# Receiver.net
KiCad netlist of a schematic drawn in Altium Designer
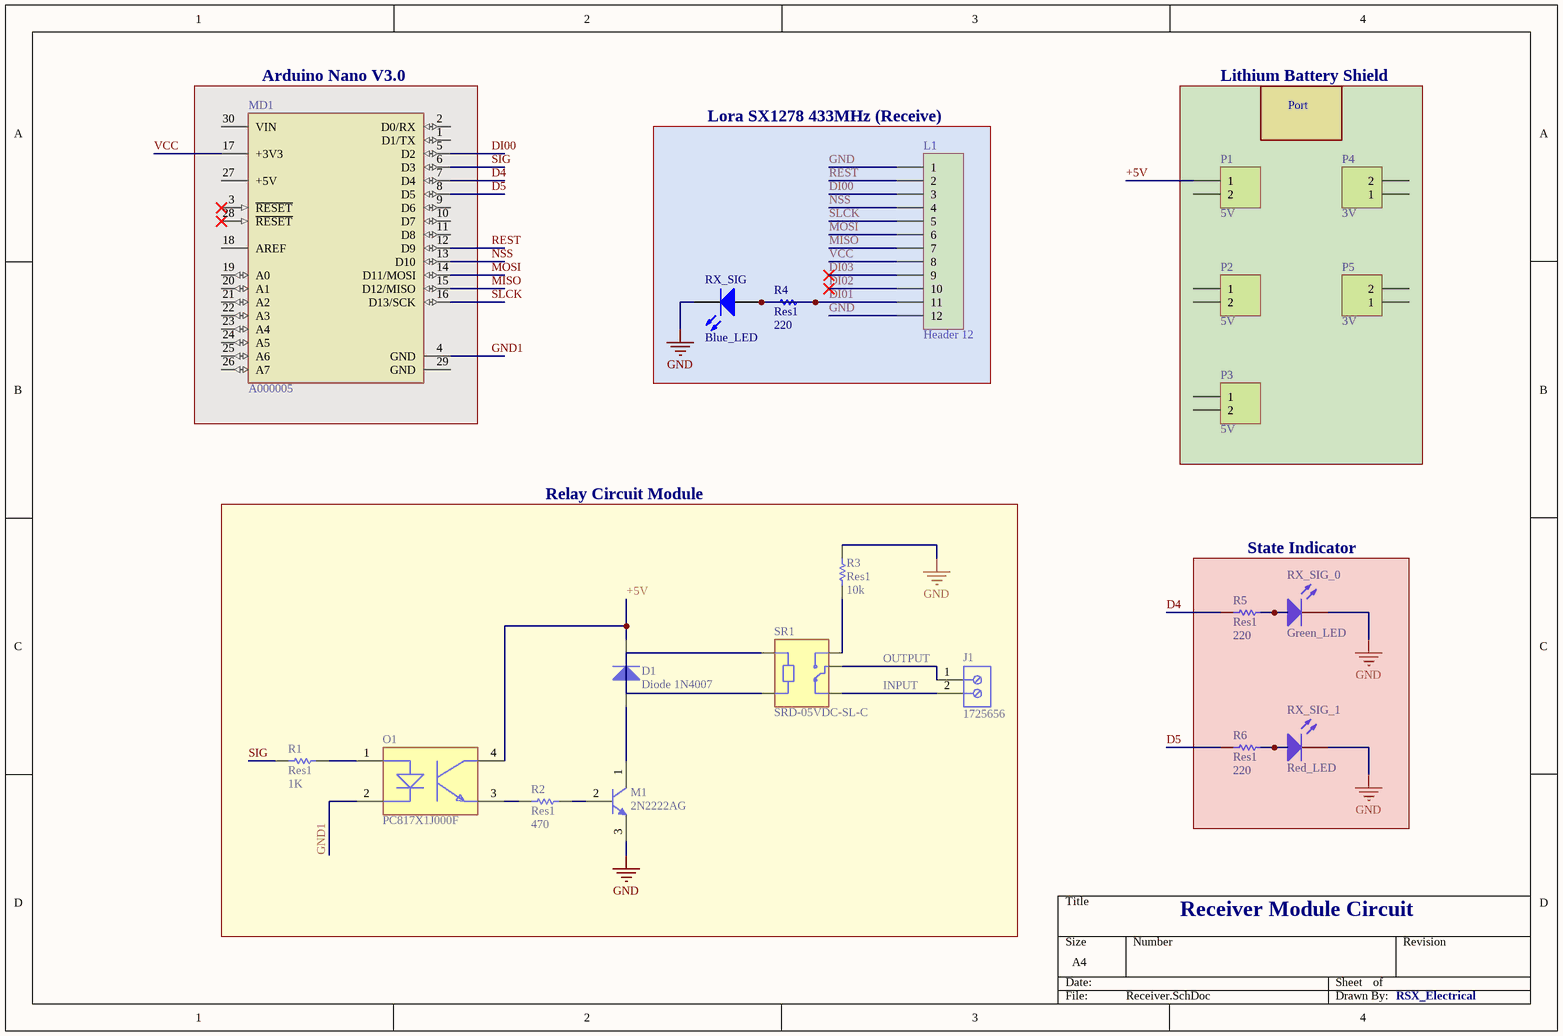
[diagram p0: Receiver.SchDoc]

(export (version "E")
  (design (tool "Eeschema 10.0.6"))
  (components
    (comp (ref "D1")
      (value "Diode 1N4007")
      (footprint "DO-41")
      (description "1 Amp General Purpose Rectifier")
      (fields (field (name "PUBLISHER") "Altium Limited"))
      (libsource (lib "Miscellaneous Devices") (part "Diode 1N4007"))
    )
    (comp (ref "J1")
      (value "1725656")
      (footprint "PHOE-1725656-2")
      (description "Male Header, Pitch 2.54 mm, 1 x 2 Position, Height 9 mm, Tail Length 3.5 mm")
      (fields (field (name "MANUFACTURER") "Phoenix Contact"))
      (libsource (lib "Altium Content Vault") (part "CN-1P-F-TB2"))
    )
    (comp (ref "L1")
      (value "Header 12")
      (footprint "HDR1X12")
      (description "Header, 12-Pin")
      (fields (field (name "PUBLISHER") "Altium Limited"))
      (libsource (lib "Miscellaneous Connectors") (part "Header 12"))
    )
    (comp (ref "M1")
      (value "2N2222AG")
      (footprint "ONSC-TO-92-3-29-11")
      (description "Amplifier Transistor, NPN Silicon, 3-Pin TO-92, Pb-Free, Bulk Box")
      (fields (field (name "PARTNUMBER") "P2N2222AG") (field (name "MANUFACTURER") "On Semiconductor"))
      (libsource (lib "Altium Content Vault") (part "ONSC-NPN-C1B2E3-3"))
    )
    (comp (ref "MD1")
      (value "A000005")
      (footprint "FP-A000005-MFG")
      (description "ARDUINO NANO ATMEGA328 EVAL BRD")
      (libsource (lib "Altium Content Vault") (part "d190c066e99afd1c6882cf92e11b2cc"))
    )
    (comp (ref "O1")
      (value "PC817X1J000F")
      (footprint "FP-PC817X1J000F-MFG")
      (description "OPTOISOLATOR 5KV TRANS 4DIP")
      (libsource (lib "Altium Content Vault") (part "8d9d817270a4e8f0d794346117f6aa3"))
    )
    (comp (ref "P1")
      (value "5V")
      (footprint "HDR1X2")
      (description "Header, 2-Pin")
      (fields (field (name "PUBLISHER") "Altium Limited"))
      (libsource (lib "") (part "Header 2_1"))
    )
    (comp (ref "P2")
      (value "5V")
      (footprint "HDR1X2")
      (description "Header, 2-Pin")
      (fields (field (name "PUBLISHER") "Altium Limited"))
      (libsource (lib "") (part "Header 2_1"))
    )
    (comp (ref "P3")
      (value "5V")
      (footprint "HDR1X2")
      (description "Header, 2-Pin")
      (fields (field (name "PUBLISHER") "Altium Limited"))
      (libsource (lib "") (part "Header 2_1"))
    )
    (comp (ref "P4")
      (value "3V")
      (footprint "HDR1X2")
      (description "Header, 2-Pin")
      (fields (field (name "PUBLISHER") "Altium Limited"))
      (libsource (lib "Miscellaneous Connectors") (part "Header 2"))
    )
    (comp (ref "P5")
      (value "3V")
      (footprint "HDR1X2")
      (description "Header, 2-Pin")
      (fields (field (name "PUBLISHER") "Altium Limited"))
      (libsource (lib "Miscellaneous Connectors") (part "Header 2"))
    )
    (comp (ref "R1")
      (value "Res1")
      (footprint "AXIAL-0.3")
      (description "Resistor")
      (fields (field (name "ALTIUM_VALUE") "1K") (field (name "PUBLISHER") "Altium Limited"))
      (libsource (lib "Miscellaneous Devices") (part "Res1"))
    )
    (comp (ref "R2")
      (value "Res1")
      (footprint "AXIAL-0.3")
      (description "Resistor")
      (fields (field (name "ALTIUM_VALUE") "470") (field (name "PUBLISHER") "Altium Limited"))
      (libsource (lib "Miscellaneous Devices") (part "Res1"))
    )
    (comp (ref "R3")
      (value "Res1")
      (footprint "AXIAL-0.3")
      (description "Resistor")
      (fields (field (name "ALTIUM_VALUE") "10k") (field (name "PUBLISHER") "Altium Limited"))
      (libsource (lib "Miscellaneous Devices") (part "Res1"))
    )
    (comp (ref "R4")
      (value "Res1")
      (footprint "AXIAL-0.3")
      (description "Resistor")
      (fields (field (name "ALTIUM_VALUE") "220") (field (name "PUBLISHER") "Altium Limited"))
      (libsource (lib "Miscellaneous Devices") (part "Res1"))
    )
    (comp (ref "R5")
      (value "Res1")
      (footprint "AXIAL-0.3")
      (description "Resistor")
      (fields (field (name "ALTIUM_VALUE") "220") (field (name "PUBLISHER") "Altium Limited"))
      (libsource (lib "Miscellaneous Devices") (part "Res1"))
    )
    (comp (ref "R6")
      (value "Res1")
      (footprint "AXIAL-0.3")
      (description "Resistor")
      (fields (field (name "ALTIUM_VALUE") "220") (field (name "PUBLISHER") "Altium Limited"))
      (libsource (lib "Miscellaneous Devices") (part "Res1"))
    )
    (comp (ref "RX_SIG")
      (value "Blue_LED")
      (footprint "LED-0")
      (description "Typical INFRARED GaAs LED")
      (fields (field (name "PUBLISHER") "Altium Limited"))
      (libsource (lib "Miscellaneous Devices") (part "LED0"))
    )
    (comp (ref "RX_SIG_0")
      (value "Green_LED")
      (footprint "LED-0")
      (description "Typical INFRARED GaAs LED")
      (fields (field (name "PUBLISHER") "Altium Limited"))
      (libsource (lib "Miscellaneous Devices") (part "LED0"))
    )
    (comp (ref "RX_SIG_1")
      (value "Red_LED")
      (footprint "LED-0")
      (description "Typical INFRARED GaAs LED")
      (fields (field (name "PUBLISHER") "Altium Limited"))
      (libsource (lib "Miscellaneous Devices") (part "LED0"))
    )
    (comp (ref "SR1")
      (value "SRD-05VDC-SL-C")
      (footprint "RELAY_SRD-05VDC-SL-C")
      (fields (field (name "MF") "Songle Relay"))
      (libsource (lib "SRD-05VDC-SL-C") (part "SRD-05VDC-SL-C"))
    )
  )
  (nets
    (net (code "1") (name "/+5V") (class "Default")
      (node (ref "D1") (pin "2") (pinfunction "K_2") (pintype "passive"))
      (node (ref "O1") (pin "4") (pinfunction "C_4") (pintype "passive"))
      (node (ref "P1") (pin "1") (pinfunction "1_1") (pintype "passive"))
    )
    (net (code "2") (name "/D4") (class "Default")
      (node (ref "MD1") (pin "7") (pinfunction "D4_7") (pintype "bidirectional"))
      (node (ref "R5") (pin "2") (pinfunction "2_2") (pintype "passive"))
    )
    (net (code "3") (name "/D5") (class "Default")
      (node (ref "MD1") (pin "8") (pinfunction "D5_8") (pintype "bidirectional"))
      (node (ref "R6") (pin "2") (pinfunction "2_2") (pintype "passive"))
    )
    (net (code "4") (name "/DI00") (class "Default")
      (node (ref "L1") (pin "3") (pinfunction "3_3") (pintype "passive"))
      (node (ref "MD1") (pin "5") (pinfunction "D2_5") (pintype "bidirectional"))
    )
    (net (code "5") (name "/DI01") (class "Default")
      (node (ref "L1") (pin "11") (pinfunction "11_11") (pintype "passive"))
      (node (ref "R4") (pin "1") (pinfunction "1_1") (pintype "passive"))
      (node (ref "R4") (pin "2") (pinfunction "2_2") (pintype "passive"))
      (node (ref "RX_SIG") (pin "1") (pinfunction "A_1") (pintype "passive"))
    )
    (net (code "6") (name "/DI02") (class "Default")
      (node (ref "L1") (pin "10") (pinfunction "10_10") (pintype "passive+no_connect"))
    )
    (net (code "7") (name "/DI03") (class "Default")
      (node (ref "L1") (pin "9") (pinfunction "9_9") (pintype "passive+no_connect"))
    )
    (net (code "8") (name "/GND1") (class "Default")
      (node (ref "MD1") (pin "4") (pinfunction "GND_4") (pintype "power_in"))
      (node (ref "O1") (pin "2") (pinfunction "C_2") (pintype "passive"))
    )
    (net (code "9") (name "/MISO") (class "Default")
      (node (ref "L1") (pin "7") (pinfunction "7_7") (pintype "passive"))
      (node (ref "MD1") (pin "15") (pinfunction "D12/MISO_15") (pintype "bidirectional"))
    )
    (net (code "10") (name "/MOSI") (class "Default")
      (node (ref "L1") (pin "6") (pinfunction "6_6") (pintype "passive"))
      (node (ref "MD1") (pin "14") (pinfunction "D11/MOSI_14") (pintype "bidirectional"))
    )
    (net (code "11") (name "/NSS") (class "Default")
      (node (ref "L1") (pin "4") (pinfunction "4_4") (pintype "passive"))
      (node (ref "MD1") (pin "13") (pinfunction "D10_13") (pintype "bidirectional"))
    )
    (net (code "12") (name "/REST") (class "Default")
      (node (ref "L1") (pin "2") (pinfunction "2_2") (pintype "passive"))
      (node (ref "MD1") (pin "12") (pinfunction "D9_12") (pintype "bidirectional"))
    )
    (net (code "13") (name "/SIG") (class "Default")
      (node (ref "MD1") (pin "6") (pinfunction "D3_6") (pintype "bidirectional"))
      (node (ref "R1") (pin "2") (pinfunction "2_2") (pintype "passive"))
    )
    (net (code "14") (name "/SLCK") (class "Default")
      (node (ref "L1") (pin "5") (pinfunction "5_5") (pintype "passive"))
      (node (ref "MD1") (pin "16") (pinfunction "D13/SCK_16") (pintype "bidirectional"))
    )
    (net (code "15") (name "/VCC") (class "Default")
      (node (ref "L1") (pin "8") (pinfunction "8_8") (pintype "passive"))
      (node (ref "MD1") (pin "17") (pinfunction "+3V3_17") (pintype "power_in"))
    )
    (net (code "16") (name "GND") (class "Default")
      (node (ref "L1") (pin "1") (pinfunction "1_1") (pintype "passive"))
      (node (ref "L1") (pin "12") (pinfunction "12_12") (pintype "passive"))
      (node (ref "M1") (pin "3") (pinfunction "E_3") (pintype "passive"))
      (node (ref "R3") (pin "2") (pinfunction "2_2") (pintype "passive"))
      (node (ref "RX_SIG") (pin "2") (pinfunction "K_2") (pintype "passive"))
      (node (ref "RX_SIG_0") (pin "2") (pinfunction "K_2") (pintype "passive"))
      (node (ref "RX_SIG_1") (pin "2") (pinfunction "K_2") (pintype "passive"))
    )
    (net (code "17") (name "Net-(D1-A)") (class "Default")
      (node (ref "D1") (pin "1") (pinfunction "A_1") (pintype "passive"))
      (node (ref "M1") (pin "1") (pinfunction "C_1") (pintype "passive"))
    )
    (net (code "18") (name "Net-(J1-Pad1)") (class "Default")
      (node (ref "J1") (pin "1") (pinfunction "1_1") (pintype "passive"))
      (node (ref "SR1") (pin "COM") (pinfunction "COM_COM") (pintype "passive"))
    )
    (net (code "19") (name "Net-(J1-Pad2)") (class "Default")
      (node (ref "J1") (pin "2") (pinfunction "2_2") (pintype "passive"))
      (node (ref "SR1") (pin "NC") (pinfunction "NC_NC") (pintype "passive"))
    )
    (net (code "20") (name "Net-(M1-B)") (class "Default")
      (node (ref "M1") (pin "2") (pinfunction "B_2") (pintype "passive"))
      (node (ref "R2") (pin "2") (pinfunction "2_2") (pintype "passive"))
    )
    (net (code "21") (name "Net-(O1-A)") (class "Default")
      (node (ref "O1") (pin "1") (pinfunction "A_1") (pintype "passive"))
      (node (ref "R1") (pin "1") (pinfunction "1_1") (pintype "passive"))
    )
    (net (code "22") (name "Net-(O1-E)") (class "Default")
      (node (ref "O1") (pin "3") (pinfunction "E_3") (pintype "passive"))
      (node (ref "R2") (pin "1") (pinfunction "1_1") (pintype "passive"))
    )
    (net (code "23") (name "Net-(R3-Pad1)") (class "Default")
      (node (ref "R3") (pin "1") (pinfunction "1_1") (pintype "passive"))
      (node (ref "SR1") (pin "NO") (pinfunction "NO_NO") (pintype "passive"))
    )
    (net (code "24") (name "Net-(RX_SIG_0-A)") (class "Default")
      (node (ref "R5") (pin "1") (pinfunction "1_1") (pintype "passive"))
      (node (ref "RX_SIG_0") (pin "1") (pinfunction "A_1") (pintype "passive"))
    )
    (net (code "25") (name "Net-(RX_SIG_1-A)") (class "Default")
      (node (ref "R6") (pin "1") (pinfunction "1_1") (pintype "passive"))
      (node (ref "RX_SIG_1") (pin "1") (pinfunction "A_1") (pintype "passive"))
    )
    (net (code "26") (name "Net-(SR1-PadA1)") (class "Default")
      (node (ref "SR1") (pin "A1") (pinfunction "A1_A1") (pintype "passive"))
      (node (ref "SR1") (pin "A2") (pinfunction "A2_A2") (pintype "passive"))
    )
    (net (code "27") (name "unconnected-(MD1-+5V-Pad27)") (class "Default")
      (node (ref "MD1") (pin "27") (pinfunction "+5V_27") (pintype "power_in"))
    )
    (net (code "28") (name "unconnected-(MD1-A0-Pad19)") (class "Default")
      (node (ref "MD1") (pin "19") (pinfunction "A0_19") (pintype "bidirectional"))
    )
    (net (code "29") (name "unconnected-(MD1-A1-Pad20)") (class "Default")
      (node (ref "MD1") (pin "20") (pinfunction "A1_20") (pintype "bidirectional"))
    )
    (net (code "30") (name "unconnected-(MD1-A2-Pad21)") (class "Default")
      (node (ref "MD1") (pin "21") (pinfunction "A2_21") (pintype "bidirectional"))
    )
    (net (code "31") (name "unconnected-(MD1-A3-Pad22)") (class "Default")
      (node (ref "MD1") (pin "22") (pinfunction "A3_22") (pintype "bidirectional"))
    )
    (net (code "32") (name "unconnected-(MD1-A4-Pad23)") (class "Default")
      (node (ref "MD1") (pin "23") (pinfunction "A4_23") (pintype "bidirectional"))
    )
    (net (code "33") (name "unconnected-(MD1-A5-Pad24)") (class "Default")
      (node (ref "MD1") (pin "24") (pinfunction "A5_24") (pintype "bidirectional"))
    )
    (net (code "34") (name "unconnected-(MD1-A6-Pad25)") (class "Default")
      (node (ref "MD1") (pin "25") (pinfunction "A6_25") (pintype "bidirectional"))
    )
    (net (code "35") (name "unconnected-(MD1-A7-Pad26)") (class "Default")
      (node (ref "MD1") (pin "26") (pinfunction "A7_26") (pintype "bidirectional"))
    )
    (net (code "36") (name "unconnected-(MD1-AREF-Pad18)") (class "Default")
      (node (ref "MD1") (pin "18") (pinfunction "AREF_18") (pintype "passive"))
    )
    (net (code "37") (name "unconnected-(MD1-D0{slash}RX-Pad2)") (class "Default")
      (node (ref "MD1") (pin "2") (pinfunction "D0/RX_2") (pintype "bidirectional"))
    )
    (net (code "38") (name "unconnected-(MD1-D1{slash}TX-Pad1)") (class "Default")
      (node (ref "MD1") (pin "1") (pinfunction "D1/TX_1") (pintype "bidirectional"))
    )
    (net (code "39") (name "unconnected-(MD1-D6-Pad9)") (class "Default")
      (node (ref "MD1") (pin "9") (pinfunction "D6_9") (pintype "bidirectional"))
    )
    (net (code "40") (name "unconnected-(MD1-D7-Pad10)") (class "Default")
      (node (ref "MD1") (pin "10") (pinfunction "D7_10") (pintype "bidirectional"))
    )
    (net (code "41") (name "unconnected-(MD1-D8-Pad11)") (class "Default")
      (node (ref "MD1") (pin "11") (pinfunction "D8_11") (pintype "bidirectional"))
    )
    (net (code "42") (name "unconnected-(MD1-GND-Pad29)") (class "Default")
      (node (ref "MD1") (pin "29") (pinfunction "GND_29") (pintype "power_in"))
    )
    (net (code "43") (name "unconnected-(MD1-VIN-Pad30)") (class "Default")
      (node (ref "MD1") (pin "30") (pinfunction "VIN_30") (pintype "power_in"))
    )
    (net (code "44") (name "unconnected-(MD1-~{RESET}-Pad3)") (class "Default")
      (node (ref "MD1") (pin "3") (pinfunction "~{RESET}_3") (pintype "input+no_connect"))
    )
    (net (code "45") (name "unconnected-(MD1-~{RESET}-Pad28)") (class "Default")
      (node (ref "MD1") (pin "28") (pinfunction "~{RESET}_28") (pintype "input+no_connect"))
    )
    (net (code "46") (name "unconnected-(P1-Pad2)") (class "Default")
      (node (ref "P1") (pin "2") (pinfunction "2_2") (pintype "passive"))
    )
    (net (code "47") (name "unconnected-(P2-Pad1)") (class "Default")
      (node (ref "P2") (pin "1") (pinfunction "1_1") (pintype "passive"))
    )
    (net (code "48") (name "unconnected-(P2-Pad2)") (class "Default")
      (node (ref "P2") (pin "2") (pinfunction "2_2") (pintype "passive"))
    )
    (net (code "49") (name "unconnected-(P3-Pad1)") (class "Default")
      (node (ref "P3") (pin "1") (pinfunction "1_1") (pintype "passive"))
    )
    (net (code "50") (name "unconnected-(P3-Pad2)") (class "Default")
      (node (ref "P3") (pin "2") (pinfunction "2_2") (pintype "passive"))
    )
    (net (code "51") (name "unconnected-(P4-Pad1)") (class "Default")
      (node (ref "P4") (pin "1") (pinfunction "1_1") (pintype "passive"))
    )
    (net (code "52") (name "unconnected-(P4-Pad2)") (class "Default")
      (node (ref "P4") (pin "2") (pinfunction "2_2") (pintype "passive"))
    )
    (net (code "53") (name "unconnected-(P5-Pad1)") (class "Default")
      (node (ref "P5") (pin "1") (pinfunction "1_1") (pintype "passive"))
    )
    (net (code "54") (name "unconnected-(P5-Pad2)") (class "Default")
      (node (ref "P5") (pin "2") (pinfunction "2_2") (pintype "passive"))
    )
  )
)
